# momav_servo.net
KiCad netlist of a schematic drawn in EAGLE
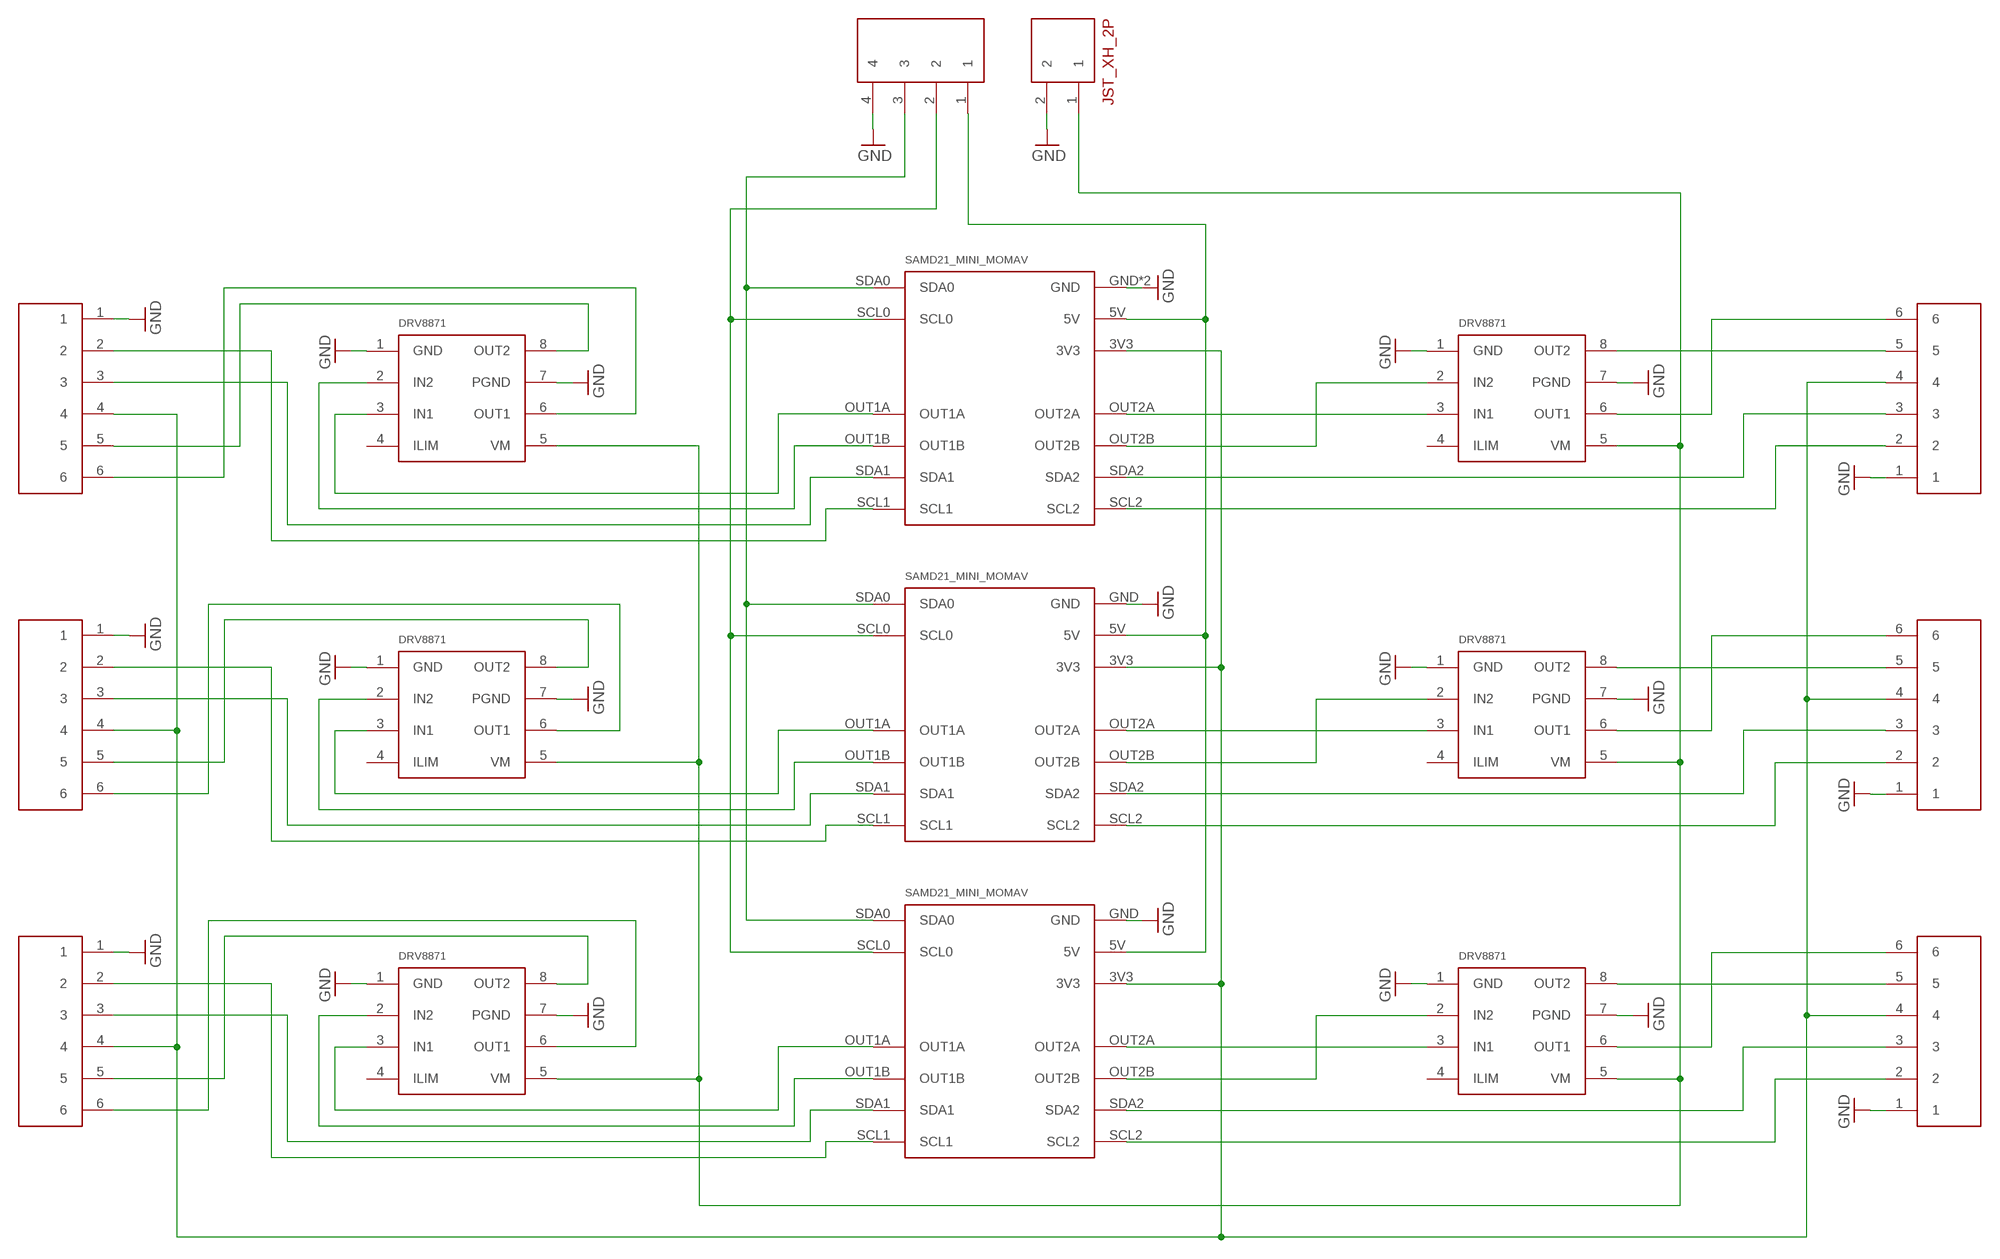
[diagram p0: schematic, sheet 1]

(export (version "E")
  (design (tool "Eeschema 10.0.6"))
  (components
    (comp (ref "U$1")
      (value "DRV8871BOB")
      (footprint "eagle-import:DRV8871BOB")
      (libsource (lib "eagle-import") (part "DRV8871BOB"))
    )
    (comp (ref "U$2")
      (value "DRV8871BOB")
      (footprint "eagle-import:DRV8871BOB")
      (libsource (lib "eagle-import") (part "DRV8871BOB"))
    )
    (comp (ref "U$3")
      (value "DRV8871BOB")
      (footprint "eagle-import:DRV8871BOB")
      (libsource (lib "eagle-import") (part "DRV8871BOB"))
    )
    (comp (ref "U$4")
      (value "DRV8871BOB")
      (footprint "eagle-import:DRV8871BOB")
      (libsource (lib "eagle-import") (part "DRV8871BOB"))
    )
    (comp (ref "U$5")
      (value "DRV8871BOB")
      (footprint "eagle-import:DRV8871BOB")
      (libsource (lib "eagle-import") (part "DRV8871BOB"))
    )
    (comp (ref "U$6")
      (value "DRV8871BOB")
      (footprint "eagle-import:DRV8871BOB")
      (libsource (lib "eagle-import") (part "DRV8871BOB"))
    )
    (comp (ref "U$7")
      (value "SAMD21_MINI_MOMAV1")
      (footprint "eagle-import:SAMD21_MINI_MOMAV1")
      (libsource (lib "eagle-import") (part "SAMD21_MINI_MOMAV1"))
    )
    (comp (ref "U$8")
      (value "SAMD21_MINI_MOMAV")
      (footprint "eagle-import:SAMD21_MINI_MOMAV")
      (libsource (lib "eagle-import") (part "SAMD21_MINI_MOMAV"))
    )
    (comp (ref "U$9")
      (value "SAMD21_MINI_MOMAV")
      (footprint "eagle-import:SAMD21_MINI_MOMAV")
      (libsource (lib "eagle-import") (part "SAMD21_MINI_MOMAV"))
    )
    (comp (ref "U$10")
      (value "JST_XH_2P")
      (footprint "eagle-import:JST_XH_2P")
      (libsource (lib "eagle-import") (part "JST_XH_2P"))
    )
    (comp (ref "U$11")
      (value "JST_ZH_4P")
      (footprint "eagle-import:JST_ZH_4P")
      (libsource (lib "eagle-import") (part "JST_ZH_4P"))
    )
    (comp (ref "U$12")
      (value "JST_ZH_6P")
      (footprint "eagle-import:JST_ZH_6P")
      (libsource (lib "eagle-import") (part "JST_ZH_6P"))
    )
    (comp (ref "U$13")
      (value "JST_ZH_6P")
      (footprint "eagle-import:JST_ZH_6P")
      (libsource (lib "eagle-import") (part "JST_ZH_6P"))
    )
    (comp (ref "U$14")
      (value "JST_ZH_6P")
      (footprint "eagle-import:JST_ZH_6P")
      (libsource (lib "eagle-import") (part "JST_ZH_6P"))
    )
    (comp (ref "U$15")
      (value "JST_ZH_6P")
      (footprint "eagle-import:JST_ZH_6P")
      (libsource (lib "eagle-import") (part "JST_ZH_6P"))
    )
    (comp (ref "U$16")
      (value "JST_ZH_6P")
      (footprint "eagle-import:JST_ZH_6P")
      (libsource (lib "eagle-import") (part "JST_ZH_6P"))
    )
    (comp (ref "U$17")
      (value "JST_ZH_6P")
      (footprint "eagle-import:JST_ZH_6P")
      (libsource (lib "eagle-import") (part "JST_ZH_6P"))
    )
  )
  (nets
    (net (code "1") (name "GND") (class "Default")
      (node (ref "U$1") (pin "1") (pinfunction "GND_1") (pintype "bidirectional"))
      (node (ref "U$1") (pin "7") (pinfunction "PGND_7") (pintype "bidirectional"))
      (node (ref "U$10") (pin "2") (pinfunction "2_2") (pintype "bidirectional"))
      (node (ref "U$11") (pin "4") (pinfunction "4_4") (pintype "bidirectional"))
      (node (ref "U$12") (pin "1") (pinfunction "1_1") (pintype "bidirectional"))
      (node (ref "U$13") (pin "1") (pinfunction "1_1") (pintype "bidirectional"))
      (node (ref "U$14") (pin "1") (pinfunction "1_1") (pintype "bidirectional"))
      (node (ref "U$15") (pin "1") (pinfunction "1_1") (pintype "bidirectional"))
      (node (ref "U$16") (pin "1") (pinfunction "1_1") (pintype "bidirectional"))
      (node (ref "U$17") (pin "1") (pinfunction "1_1") (pintype "bidirectional"))
      (node (ref "U$2") (pin "1") (pinfunction "GND_1") (pintype "bidirectional"))
      (node (ref "U$2") (pin "7") (pinfunction "PGND_7") (pintype "bidirectional"))
      (node (ref "U$3") (pin "1") (pinfunction "GND_1") (pintype "bidirectional"))
      (node (ref "U$3") (pin "7") (pinfunction "PGND_7") (pintype "bidirectional"))
      (node (ref "U$4") (pin "1") (pinfunction "GND_1") (pintype "bidirectional"))
      (node (ref "U$4") (pin "7") (pinfunction "PGND_7") (pintype "bidirectional"))
      (node (ref "U$5") (pin "1") (pinfunction "GND_1") (pintype "bidirectional"))
      (node (ref "U$5") (pin "7") (pinfunction "PGND_7") (pintype "bidirectional"))
      (node (ref "U$6") (pin "1") (pinfunction "GND_1") (pintype "bidirectional"))
      (node (ref "U$6") (pin "7") (pinfunction "PGND_7") (pintype "bidirectional"))
      (node (ref "U$7") (pin "GND") (pinfunction "GND_GND") (pintype "bidirectional"))
      (node (ref "U$7") (pin "GND2") (pinfunction "GND_GND2") (pintype "bidirectional"))
      (node (ref "U$8") (pin "GND") (pinfunction "GND_GND") (pintype "bidirectional"))
      (node (ref "U$9") (pin "GND") (pinfunction "GND_GND") (pintype "bidirectional"))
    )
    (net (code "2") (name "Net-(U$1-IN1)") (class "Default")
      (node (ref "U$1") (pin "3") (pinfunction "IN1_3") (pintype "bidirectional"))
      (node (ref "U$7") (pin "OUT1A") (pinfunction "OUT1A_OUT1A") (pintype "bidirectional"))
    )
    (net (code "3") (name "Net-(U$1-IN2)") (class "Default")
      (node (ref "U$1") (pin "2") (pinfunction "IN2_2") (pintype "bidirectional"))
      (node (ref "U$7") (pin "OUT1B") (pinfunction "OUT1B_OUT1B") (pintype "bidirectional"))
    )
    (net (code "4") (name "Net-(U$1-OUT1)") (class "Default")
      (node (ref "U$1") (pin "6") (pinfunction "OUT1_6") (pintype "bidirectional"))
      (node (ref "U$12") (pin "6") (pinfunction "6_6") (pintype "bidirectional"))
    )
    (net (code "5") (name "Net-(U$1-OUT2)") (class "Default")
      (node (ref "U$1") (pin "8") (pinfunction "OUT2_8") (pintype "bidirectional"))
      (node (ref "U$12") (pin "5") (pinfunction "5_5") (pintype "bidirectional"))
    )
    (net (code "6") (name "Net-(U$1-VM)") (class "Default")
      (node (ref "U$1") (pin "5") (pinfunction "VM_5") (pintype "bidirectional"))
      (node (ref "U$10") (pin "1") (pinfunction "1_1") (pintype "bidirectional"))
      (node (ref "U$2") (pin "5") (pinfunction "VM_5") (pintype "bidirectional"))
      (node (ref "U$3") (pin "5") (pinfunction "VM_5") (pintype "bidirectional"))
      (node (ref "U$4") (pin "5") (pinfunction "VM_5") (pintype "bidirectional"))
      (node (ref "U$5") (pin "5") (pinfunction "VM_5") (pintype "bidirectional"))
      (node (ref "U$6") (pin "5") (pinfunction "VM_5") (pintype "bidirectional"))
    )
    (net (code "7") (name "Net-(U$2-IN1)") (class "Default")
      (node (ref "U$2") (pin "3") (pinfunction "IN1_3") (pintype "bidirectional"))
      (node (ref "U$8") (pin "OUT1A") (pinfunction "OUT1A_OUT1A") (pintype "bidirectional"))
    )
    (net (code "8") (name "Net-(U$2-IN2)") (class "Default")
      (node (ref "U$2") (pin "2") (pinfunction "IN2_2") (pintype "bidirectional"))
      (node (ref "U$8") (pin "OUT1B") (pinfunction "OUT1B_OUT1B") (pintype "bidirectional"))
    )
    (net (code "9") (name "Net-(U$2-OUT1)") (class "Default")
      (node (ref "U$13") (pin "6") (pinfunction "6_6") (pintype "bidirectional"))
      (node (ref "U$2") (pin "6") (pinfunction "OUT1_6") (pintype "bidirectional"))
    )
    (net (code "10") (name "Net-(U$2-OUT2)") (class "Default")
      (node (ref "U$13") (pin "5") (pinfunction "5_5") (pintype "bidirectional"))
      (node (ref "U$2") (pin "8") (pinfunction "OUT2_8") (pintype "bidirectional"))
    )
    (net (code "11") (name "Net-(U$3-IN1)") (class "Default")
      (node (ref "U$3") (pin "3") (pinfunction "IN1_3") (pintype "bidirectional"))
      (node (ref "U$9") (pin "OUT1A") (pinfunction "OUT1A_OUT1A") (pintype "bidirectional"))
    )
    (net (code "12") (name "Net-(U$3-IN2)") (class "Default")
      (node (ref "U$3") (pin "2") (pinfunction "IN2_2") (pintype "bidirectional"))
      (node (ref "U$9") (pin "OUT1B") (pinfunction "OUT1B_OUT1B") (pintype "bidirectional"))
    )
    (net (code "13") (name "Net-(U$3-OUT1)") (class "Default")
      (node (ref "U$14") (pin "6") (pinfunction "6_6") (pintype "bidirectional"))
      (node (ref "U$3") (pin "6") (pinfunction "OUT1_6") (pintype "bidirectional"))
    )
    (net (code "14") (name "Net-(U$3-OUT2)") (class "Default")
      (node (ref "U$14") (pin "5") (pinfunction "5_5") (pintype "bidirectional"))
      (node (ref "U$3") (pin "8") (pinfunction "OUT2_8") (pintype "bidirectional"))
    )
    (net (code "15") (name "Net-(U$4-IN1)") (class "Default")
      (node (ref "U$4") (pin "3") (pinfunction "IN1_3") (pintype "bidirectional"))
      (node (ref "U$7") (pin "OUT2A") (pinfunction "OUT2A_OUT2A") (pintype "bidirectional"))
    )
    (net (code "16") (name "Net-(U$4-IN2)") (class "Default")
      (node (ref "U$4") (pin "2") (pinfunction "IN2_2") (pintype "bidirectional"))
      (node (ref "U$7") (pin "OUT2B") (pinfunction "OUT2B_OUT2B") (pintype "bidirectional"))
    )
    (net (code "17") (name "Net-(U$4-OUT1)") (class "Default")
      (node (ref "U$17") (pin "6") (pinfunction "6_6") (pintype "bidirectional"))
      (node (ref "U$4") (pin "6") (pinfunction "OUT1_6") (pintype "bidirectional"))
    )
    (net (code "18") (name "Net-(U$4-OUT2)") (class "Default")
      (node (ref "U$17") (pin "5") (pinfunction "5_5") (pintype "bidirectional"))
      (node (ref "U$4") (pin "8") (pinfunction "OUT2_8") (pintype "bidirectional"))
    )
    (net (code "19") (name "Net-(U$5-IN1)") (class "Default")
      (node (ref "U$5") (pin "3") (pinfunction "IN1_3") (pintype "bidirectional"))
      (node (ref "U$8") (pin "OUT2A") (pinfunction "OUT2A_OUT2A") (pintype "bidirectional"))
    )
    (net (code "20") (name "Net-(U$5-IN2)") (class "Default")
      (node (ref "U$5") (pin "2") (pinfunction "IN2_2") (pintype "bidirectional"))
      (node (ref "U$8") (pin "OUT2B") (pinfunction "OUT2B_OUT2B") (pintype "bidirectional"))
    )
    (net (code "21") (name "Net-(U$5-OUT1)") (class "Default")
      (node (ref "U$16") (pin "6") (pinfunction "6_6") (pintype "bidirectional"))
      (node (ref "U$5") (pin "6") (pinfunction "OUT1_6") (pintype "bidirectional"))
    )
    (net (code "22") (name "Net-(U$5-OUT2)") (class "Default")
      (node (ref "U$16") (pin "5") (pinfunction "5_5") (pintype "bidirectional"))
      (node (ref "U$5") (pin "8") (pinfunction "OUT2_8") (pintype "bidirectional"))
    )
    (net (code "23") (name "Net-(U$6-IN1)") (class "Default")
      (node (ref "U$6") (pin "3") (pinfunction "IN1_3") (pintype "bidirectional"))
      (node (ref "U$9") (pin "OUT2A") (pinfunction "OUT2A_OUT2A") (pintype "bidirectional"))
    )
    (net (code "24") (name "Net-(U$6-IN2)") (class "Default")
      (node (ref "U$6") (pin "2") (pinfunction "IN2_2") (pintype "bidirectional"))
      (node (ref "U$9") (pin "OUT2B") (pinfunction "OUT2B_OUT2B") (pintype "bidirectional"))
    )
    (net (code "25") (name "Net-(U$6-OUT1)") (class "Default")
      (node (ref "U$15") (pin "6") (pinfunction "6_6") (pintype "bidirectional"))
      (node (ref "U$6") (pin "6") (pinfunction "OUT1_6") (pintype "bidirectional"))
    )
    (net (code "26") (name "Net-(U$6-OUT2)") (class "Default")
      (node (ref "U$15") (pin "5") (pinfunction "5_5") (pintype "bidirectional"))
      (node (ref "U$6") (pin "8") (pinfunction "OUT2_8") (pintype "bidirectional"))
    )
    (net (code "27") (name "Net-(U$11-Pad1)") (class "Default")
      (node (ref "U$11") (pin "1") (pinfunction "1_1") (pintype "bidirectional"))
      (node (ref "U$7") (pin "5V") (pinfunction "5V_5V") (pintype "bidirectional"))
      (node (ref "U$8") (pin "5V") (pinfunction "5V_5V") (pintype "bidirectional"))
      (node (ref "U$9") (pin "5V") (pinfunction "5V_5V") (pintype "bidirectional"))
    )
    (net (code "28") (name "Net-(U$11-Pad2)") (class "Default")
      (node (ref "U$11") (pin "2") (pinfunction "2_2") (pintype "bidirectional"))
      (node (ref "U$7") (pin "SCL0") (pinfunction "SCL0_SCL0") (pintype "bidirectional"))
      (node (ref "U$8") (pin "SCL0") (pinfunction "SCL0_SCL0") (pintype "bidirectional"))
      (node (ref "U$9") (pin "SCL0") (pinfunction "SCL0_SCL0") (pintype "bidirectional"))
    )
    (net (code "29") (name "Net-(U$11-Pad3)") (class "Default")
      (node (ref "U$11") (pin "3") (pinfunction "3_3") (pintype "bidirectional"))
      (node (ref "U$7") (pin "SDA0") (pinfunction "SDA0_SDA0") (pintype "bidirectional"))
      (node (ref "U$8") (pin "SDA0") (pinfunction "SDA0_SDA0") (pintype "bidirectional"))
      (node (ref "U$9") (pin "SDA0") (pinfunction "SDA0_SDA0") (pintype "bidirectional"))
    )
    (net (code "30") (name "Net-(U$12-Pad2)") (class "Default")
      (node (ref "U$12") (pin "2") (pinfunction "2_2") (pintype "bidirectional"))
      (node (ref "U$7") (pin "SCL1") (pinfunction "SCL1_SCL1") (pintype "bidirectional"))
    )
    (net (code "31") (name "Net-(U$12-Pad3)") (class "Default")
      (node (ref "U$12") (pin "3") (pinfunction "3_3") (pintype "bidirectional"))
      (node (ref "U$7") (pin "SDA1") (pinfunction "SDA1_SDA1") (pintype "bidirectional"))
    )
    (net (code "32") (name "Net-(U$12-Pad4)") (class "Default")
      (node (ref "U$12") (pin "4") (pinfunction "4_4") (pintype "bidirectional"))
      (node (ref "U$13") (pin "4") (pinfunction "4_4") (pintype "bidirectional"))
      (node (ref "U$14") (pin "4") (pinfunction "4_4") (pintype "bidirectional"))
      (node (ref "U$15") (pin "4") (pinfunction "4_4") (pintype "bidirectional"))
      (node (ref "U$16") (pin "4") (pinfunction "4_4") (pintype "bidirectional"))
      (node (ref "U$17") (pin "4") (pinfunction "4_4") (pintype "bidirectional"))
      (node (ref "U$7") (pin "3V3") (pinfunction "3V3_3V3") (pintype "bidirectional"))
      (node (ref "U$8") (pin "3V3") (pinfunction "3V3_3V3") (pintype "bidirectional"))
      (node (ref "U$9") (pin "3V3") (pinfunction "3V3_3V3") (pintype "bidirectional"))
    )
    (net (code "33") (name "Net-(U$13-Pad2)") (class "Default")
      (node (ref "U$13") (pin "2") (pinfunction "2_2") (pintype "bidirectional"))
      (node (ref "U$8") (pin "SCL1") (pinfunction "SCL1_SCL1") (pintype "bidirectional"))
    )
    (net (code "34") (name "Net-(U$13-Pad3)") (class "Default")
      (node (ref "U$13") (pin "3") (pinfunction "3_3") (pintype "bidirectional"))
      (node (ref "U$8") (pin "SDA1") (pinfunction "SDA1_SDA1") (pintype "bidirectional"))
    )
    (net (code "35") (name "Net-(U$14-Pad2)") (class "Default")
      (node (ref "U$14") (pin "2") (pinfunction "2_2") (pintype "bidirectional"))
      (node (ref "U$9") (pin "SCL1") (pinfunction "SCL1_SCL1") (pintype "bidirectional"))
    )
    (net (code "36") (name "Net-(U$14-Pad3)") (class "Default")
      (node (ref "U$14") (pin "3") (pinfunction "3_3") (pintype "bidirectional"))
      (node (ref "U$9") (pin "SDA1") (pinfunction "SDA1_SDA1") (pintype "bidirectional"))
    )
    (net (code "37") (name "Net-(U$15-Pad2)") (class "Default")
      (node (ref "U$15") (pin "2") (pinfunction "2_2") (pintype "bidirectional"))
      (node (ref "U$9") (pin "SCL2") (pinfunction "SCL2_SCL2") (pintype "bidirectional"))
    )
    (net (code "38") (name "Net-(U$15-Pad3)") (class "Default")
      (node (ref "U$15") (pin "3") (pinfunction "3_3") (pintype "bidirectional"))
      (node (ref "U$9") (pin "SDA2") (pinfunction "SDA2_SDA2") (pintype "bidirectional"))
    )
    (net (code "39") (name "Net-(U$16-Pad2)") (class "Default")
      (node (ref "U$16") (pin "2") (pinfunction "2_2") (pintype "bidirectional"))
      (node (ref "U$8") (pin "SCL2") (pinfunction "SCL2_SCL2") (pintype "bidirectional"))
    )
    (net (code "40") (name "Net-(U$16-Pad3)") (class "Default")
      (node (ref "U$16") (pin "3") (pinfunction "3_3") (pintype "bidirectional"))
      (node (ref "U$8") (pin "SDA2") (pinfunction "SDA2_SDA2") (pintype "bidirectional"))
    )
    (net (code "41") (name "Net-(U$17-Pad2)") (class "Default")
      (node (ref "U$17") (pin "2") (pinfunction "2_2") (pintype "bidirectional"))
      (node (ref "U$7") (pin "SCL2") (pinfunction "SCL2_SCL2") (pintype "bidirectional"))
    )
    (net (code "42") (name "Net-(U$17-Pad3)") (class "Default")
      (node (ref "U$17") (pin "3") (pinfunction "3_3") (pintype "bidirectional"))
      (node (ref "U$7") (pin "SDA2") (pinfunction "SDA2_SDA2") (pintype "bidirectional"))
    )
    (net (code "43") (name "unconnected-(U$1-ILIM-Pad4)") (class "Default")
      (node (ref "U$1") (pin "4") (pinfunction "ILIM_4") (pintype "bidirectional"))
    )
    (net (code "44") (name "unconnected-(U$2-ILIM-Pad4)") (class "Default")
      (node (ref "U$2") (pin "4") (pinfunction "ILIM_4") (pintype "bidirectional"))
    )
    (net (code "45") (name "unconnected-(U$3-ILIM-Pad4)") (class "Default")
      (node (ref "U$3") (pin "4") (pinfunction "ILIM_4") (pintype "bidirectional"))
    )
    (net (code "46") (name "unconnected-(U$4-ILIM-Pad4)") (class "Default")
      (node (ref "U$4") (pin "4") (pinfunction "ILIM_4") (pintype "bidirectional"))
    )
    (net (code "47") (name "unconnected-(U$5-ILIM-Pad4)") (class "Default")
      (node (ref "U$5") (pin "4") (pinfunction "ILIM_4") (pintype "bidirectional"))
    )
    (net (code "48") (name "unconnected-(U$6-ILIM-Pad4)") (class "Default")
      (node (ref "U$6") (pin "4") (pinfunction "ILIM_4") (pintype "bidirectional"))
    )
  )
)
